# currentplank.net
KiCad netlist of a schematic drawn in EAGLE
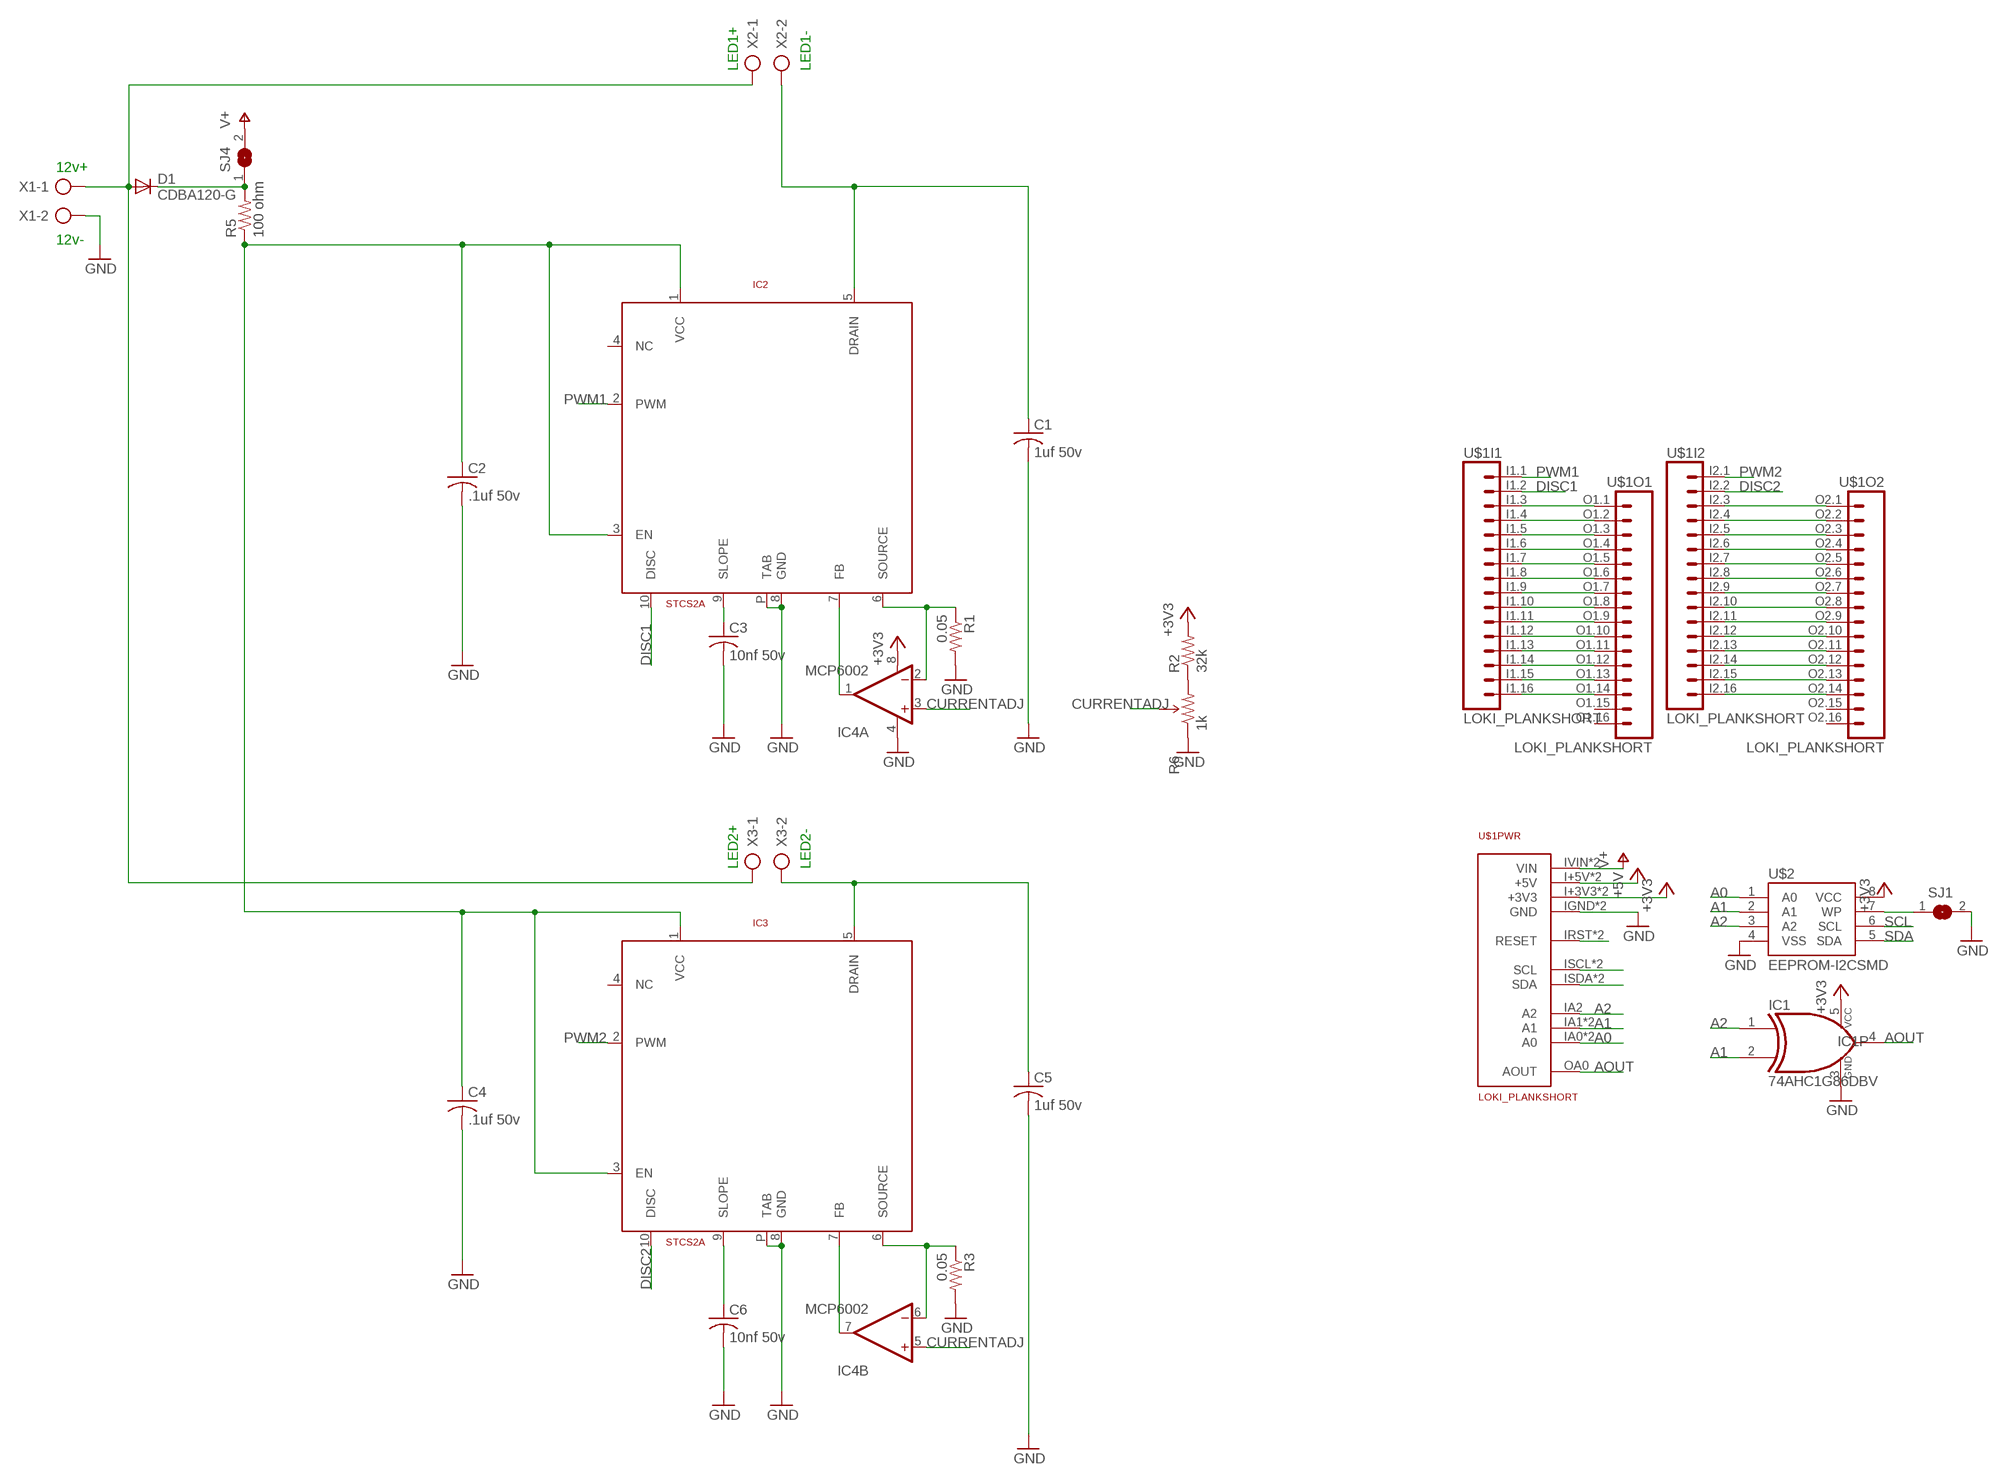
[diagram p0: schematic, sheet 1]

(export (version "E")
  (design (tool "Eeschema 10.0.6"))
  (components
    (comp (ref "C1")
      (value "1uf 50v")
      (footprint "eagle-import:C0805")
      (libsource (lib "eagle-import") (part "C-USC0805"))
    )
    (comp (ref "C2")
      (value ".1uf 50v")
      (footprint "eagle-import:C0805")
      (libsource (lib "eagle-import") (part "C-USC0805"))
    )
    (comp (ref "C3")
      (value "10nf 50v")
      (footprint "eagle-import:C0805")
      (libsource (lib "eagle-import") (part "C-USC0805"))
    )
    (comp (ref "C4")
      (value ".1uf 50v")
      (footprint "eagle-import:C0805")
      (libsource (lib "eagle-import") (part "C-USC0805"))
    )
    (comp (ref "C5")
      (value "1uf 50v")
      (footprint "eagle-import:C0805")
      (libsource (lib "eagle-import") (part "C-USC0805"))
    )
    (comp (ref "C6")
      (value "10nf 50v")
      (footprint "eagle-import:C0805")
      (libsource (lib "eagle-import") (part "C-USC0805"))
    )
    (comp (ref "D1")
      (value "CDBA120-G")
      (footprint "eagle-import:SMA-DIODE")
      (libsource (lib "eagle-import") (part "DIODESMA"))
    )
    (comp (ref "IC1")
      (value "74AHC1G86DBV")
      (footprint "eagle-import:SOT23-5")
      (libsource (lib "eagle-import") (part "741G86DBVAHC"))
    )
    (comp (ref "IC2")
      (value "STCS2A")
      (footprint "eagle-import:STCS2A_POWER-SO10")
      (libsource (lib "eagle-import") (part "STCS2A_STCS2A"))
    )
    (comp (ref "IC3")
      (value "STCS2A")
      (footprint "eagle-import:STCS2A_POWER-SO10")
      (libsource (lib "eagle-import") (part "STCS2A_STCS2A"))
    )
    (comp (ref "IC4")
      (value "MCP6002")
      (footprint "eagle-import:SO08")
      (libsource (lib "eagle-import") (part "OPAMP-DUALU"))
    )
    (comp (ref "R1")
      (value "0.05")
      (footprint "eagle-import:1206")
      (libsource (lib "eagle-import") (part "RESISTOR1206"))
    )
    (comp (ref "R2")
      (value "32k")
      (footprint "eagle-import:0805")
      (libsource (lib "eagle-import") (part "RESISTOR0805-RES"))
    )
    (comp (ref "R3")
      (value "0.05")
      (footprint "eagle-import:1206")
      (libsource (lib "eagle-import") (part "RESISTOR1206"))
    )
    (comp (ref "R5")
      (value "100 ohm")
      (footprint "eagle-import:0805")
      (libsource (lib "eagle-import") (part "RESISTOR0805-RES"))
    )
    (comp (ref "R6")
      (value "1k")
      (footprint "eagle-import:TRIMPOT-3MM-2")
      (libsource (lib "eagle-import") (part "TRIMPOT3MM-2"))
    )
    (comp (ref "SJ1") (value "SJ") (footprint "eagle-import:SJ") (libsource (lib "eagle-import") (part "SJ")))
    (comp (ref "SJ4") (value "SJ") (footprint "eagle-import:SJ") (libsource (lib "eagle-import") (part "SJ")))
    (comp (ref "U$1")
      (value "LOKI_PLANKSHORT")
      (footprint "eagle-import:PLANK_SHORT")
      (libsource (lib "eagle-import") (part "LOKI_PLANKSHORT"))
    )
    (comp (ref "U$2")
      (value "EEPROM-I2CSMD")
      (footprint "eagle-import:SO08")
      (libsource (lib "eagle-import") (part "EEPROM-I2CSMD"))
    )
    (comp (ref "X1")
      (value "AK500/2-H")
      (footprint "eagle-import:AK500_2-H")
      (libsource (lib "eagle-import") (part "AK500/2-H"))
    )
    (comp (ref "X2")
      (value "AK500/2-H")
      (footprint "eagle-import:AK500_2-H")
      (libsource (lib "eagle-import") (part "AK500/2-H"))
    )
    (comp (ref "X3")
      (value "AK500/2-H")
      (footprint "eagle-import:AK500_2-H")
      (libsource (lib "eagle-import") (part "AK500/2-H"))
    )
  )
  (nets
    (net (code "1") (name "+3V3") (class "Default")
      (node (ref "IC1") (pin "5") (pinfunction "VCC_5") (pintype "power_in"))
      (node (ref "IC4") (pin "8") (pinfunction "V+_8") (pintype "power_in"))
      (node (ref "R2") (pin "2") (pinfunction "2_2") (pintype "passive"))
      (node (ref "U$1") (pin "I+3V3") (pinfunction "+3V3_I+3V3") (pintype "power_in"))
      (node (ref "U$1") (pin "O+3V3") (pinfunction "+3V3_O+3V3") (pintype "power_in"))
      (node (ref "U$2") (pin "8") (pinfunction "VCC_8") (pintype "power_in"))
    )
    (net (code "2") (name "+5V") (class "Default")
      (node (ref "U$1") (pin "I+5V") (pinfunction "+5V_I+5V") (pintype "power_in"))
      (node (ref "U$1") (pin "O+5V") (pinfunction "+5V_O+5V") (pintype "power_in"))
    )
    (net (code "3") (name "/A0") (class "Default")
      (node (ref "U$1") (pin "IA0") (pinfunction "A0_IA0") (pintype "output"))
      (node (ref "U$1") (pin "OA1") (pinfunction "A0_OA1") (pintype "output"))
      (node (ref "U$2") (pin "1") (pinfunction "A0_1") (pintype "bidirectional"))
    )
    (net (code "4") (name "/A1") (class "Default")
      (node (ref "IC1") (pin "2") (pinfunction "I1_2") (pintype "input"))
      (node (ref "U$1") (pin "IA1") (pinfunction "A1_IA1") (pintype "output"))
      (node (ref "U$1") (pin "OA2") (pinfunction "A1_OA2") (pintype "output"))
      (node (ref "U$2") (pin "2") (pinfunction "A1_2") (pintype "bidirectional"))
    )
    (net (code "5") (name "/A2") (class "Default")
      (node (ref "IC1") (pin "1") (pinfunction "I0_1") (pintype "input"))
      (node (ref "U$1") (pin "IA2") (pinfunction "A2_IA2") (pintype "output"))
      (node (ref "U$2") (pin "3") (pinfunction "A2_3") (pintype "bidirectional"))
    )
    (net (code "6") (name "/AOUT") (class "Default")
      (node (ref "IC1") (pin "4") (pinfunction "O_4") (pintype "output"))
      (node (ref "U$1") (pin "OA0") (pinfunction "AOUT_OA0") (pintype "input"))
    )
    (net (code "7") (name "/CURRENTADJ") (class "Default")
      (node (ref "IC4") (pin "3") (pinfunction "+IN_3") (pintype "input"))
      (node (ref "IC4") (pin "5") (pinfunction "+IN_5") (pintype "input"))
      (node (ref "R6") (pin "2") (pinfunction "WIPER_2") (pintype "passive"))
    )
    (net (code "8") (name "/DISC1") (class "Default")
      (node (ref "IC2") (pin "10") (pinfunction "DISC_10") (pintype "output"))
      (node (ref "U$1") (pin "I1.2") (pinfunction "2_I1.2") (pintype "passive"))
    )
    (net (code "9") (name "/DISC2") (class "Default")
      (node (ref "IC3") (pin "10") (pinfunction "DISC_10") (pintype "output"))
      (node (ref "U$1") (pin "I2.2") (pinfunction "2_I2.2") (pintype "passive"))
    )
    (net (code "10") (name "/PWM1") (class "Default")
      (node (ref "IC2") (pin "2") (pinfunction "PWM_2") (pintype "input"))
      (node (ref "U$1") (pin "I1.1") (pinfunction "1_I1.1") (pintype "passive"))
    )
    (net (code "11") (name "/PWM2") (class "Default")
      (node (ref "IC3") (pin "2") (pinfunction "PWM_2") (pintype "input"))
      (node (ref "U$1") (pin "I2.1") (pinfunction "1_I2.1") (pintype "passive"))
    )
    (net (code "12") (name "/SCL") (class "Default")
      (node (ref "U$1") (pin "ISCL") (pinfunction "SCL_ISCL") (pintype "bidirectional"))
      (node (ref "U$1") (pin "OSCL") (pinfunction "SCL_OSCL") (pintype "bidirectional"))
      (node (ref "U$2") (pin "6") (pinfunction "SCL_6") (pintype "bidirectional"))
    )
    (net (code "13") (name "/SDA") (class "Default")
      (node (ref "U$1") (pin "ISDA") (pinfunction "SDA_ISDA") (pintype "bidirectional"))
      (node (ref "U$1") (pin "OSDA") (pinfunction "SDA_OSDA") (pintype "bidirectional"))
      (node (ref "U$2") (pin "5") (pinfunction "SDA_5") (pintype "bidirectional"))
    )
    (net (code "14") (name "GND") (class "Default")
      (node (ref "C1") (pin "2") (pinfunction "2_2") (pintype "passive"))
      (node (ref "C2") (pin "2") (pinfunction "2_2") (pintype "passive"))
      (node (ref "C3") (pin "2") (pinfunction "2_2") (pintype "passive"))
      (node (ref "C4") (pin "2") (pinfunction "2_2") (pintype "passive"))
      (node (ref "C5") (pin "2") (pinfunction "2_2") (pintype "passive"))
      (node (ref "C6") (pin "2") (pinfunction "2_2") (pintype "passive"))
      (node (ref "IC1") (pin "3") (pinfunction "GND_3") (pintype "power_in"))
      (node (ref "IC2") (pin "8") (pinfunction "GND_8") (pintype "power_in"))
      (node (ref "IC2") (pin "P") (pinfunction "TAB_P") (pintype "power_in"))
      (node (ref "IC3") (pin "8") (pinfunction "GND_8") (pintype "power_in"))
      (node (ref "IC3") (pin "P") (pinfunction "TAB_P") (pintype "power_in"))
      (node (ref "IC4") (pin "4") (pinfunction "V-_4") (pintype "power_in"))
      (node (ref "R1") (pin "2") (pinfunction "2_2") (pintype "passive"))
      (node (ref "R3") (pin "2") (pinfunction "2_2") (pintype "passive"))
      (node (ref "R6") (pin "1") (pinfunction "CCW_1") (pintype "passive"))
      (node (ref "SJ1") (pin "2") (pinfunction "2_2") (pintype "passive"))
      (node (ref "U$1") (pin "IGND") (pinfunction "GND_IGND") (pintype "power_in"))
      (node (ref "U$1") (pin "OGND") (pinfunction "GND_OGND") (pintype "power_in"))
      (node (ref "U$2") (pin "4") (pinfunction "VSS_4") (pintype "power_in"))
      (node (ref "X1") (pin "2") (pinfunction "KL_2") (pintype "passive"))
    )
    (net (code "15") (name "Net-(D1-PadC)") (class "Default")
      (node (ref "D1") (pin "C") (pinfunction "C_C") (pintype "passive"))
      (node (ref "R5") (pin "2") (pinfunction "2_2") (pintype "passive"))
      (node (ref "SJ4") (pin "1") (pinfunction "1_1") (pintype "passive"))
    )
    (net (code "16") (name "Net-(IC2-DRAIN)") (class "Default")
      (node (ref "C1") (pin "1") (pinfunction "1_1") (pintype "passive"))
      (node (ref "IC2") (pin "5") (pinfunction "DRAIN_5") (pintype "input"))
      (node (ref "X2") (pin "2") (pinfunction "KL_2") (pintype "passive"))
    )
    (net (code "17") (name "Net-(IC2-EN)") (class "Default")
      (node (ref "C2") (pin "1") (pinfunction "1_1") (pintype "passive"))
      (node (ref "C4") (pin "1") (pinfunction "1_1") (pintype "passive"))
      (node (ref "IC2") (pin "1") (pinfunction "VCC_1") (pintype "power_in"))
      (node (ref "IC2") (pin "3") (pinfunction "EN_3") (pintype "input"))
      (node (ref "IC3") (pin "1") (pinfunction "VCC_1") (pintype "power_in"))
      (node (ref "IC3") (pin "3") (pinfunction "EN_3") (pintype "input"))
      (node (ref "R5") (pin "1") (pinfunction "1_1") (pintype "passive"))
    )
    (net (code "18") (name "Net-(IC2-FB)") (class "Default")
      (node (ref "IC2") (pin "7") (pinfunction "FB_7") (pintype "input"))
      (node (ref "IC4") (pin "1") (pinfunction "OUT_1") (pintype "output"))
    )
    (net (code "19") (name "Net-(IC2-SLOPE)") (class "Default")
      (node (ref "C3") (pin "1") (pinfunction "1_1") (pintype "passive"))
      (node (ref "IC2") (pin "9") (pinfunction "SLOPE_9") (pintype "passive"))
    )
    (net (code "20") (name "Net-(IC2-SOURCE)") (class "Default")
      (node (ref "IC2") (pin "6") (pinfunction "SOURCE_6") (pintype "output"))
      (node (ref "IC4") (pin "2") (pinfunction "-IN_2") (pintype "input"))
      (node (ref "R1") (pin "1") (pinfunction "1_1") (pintype "passive"))
    )
    (net (code "21") (name "Net-(IC3-DRAIN)") (class "Default")
      (node (ref "C5") (pin "1") (pinfunction "1_1") (pintype "passive"))
      (node (ref "IC3") (pin "5") (pinfunction "DRAIN_5") (pintype "input"))
      (node (ref "X3") (pin "2") (pinfunction "KL_2") (pintype "passive"))
    )
    (net (code "22") (name "Net-(IC3-FB)") (class "Default")
      (node (ref "IC3") (pin "7") (pinfunction "FB_7") (pintype "input"))
      (node (ref "IC4") (pin "7") (pinfunction "OUT_7") (pintype "output"))
    )
    (net (code "23") (name "Net-(IC3-SLOPE)") (class "Default")
      (node (ref "C6") (pin "1") (pinfunction "1_1") (pintype "passive"))
      (node (ref "IC3") (pin "9") (pinfunction "SLOPE_9") (pintype "passive"))
    )
    (net (code "24") (name "Net-(IC3-SOURCE)") (class "Default")
      (node (ref "IC3") (pin "6") (pinfunction "SOURCE_6") (pintype "output"))
      (node (ref "IC4") (pin "6") (pinfunction "-IN_6") (pintype "input"))
      (node (ref "R3") (pin "1") (pinfunction "1_1") (pintype "passive"))
    )
    (net (code "25") (name "Net-(R6-CW)") (class "Default")
      (node (ref "R2") (pin "1") (pinfunction "1_1") (pintype "passive"))
      (node (ref "R6") (pin "3") (pinfunction "CW_3") (pintype "passive"))
    )
    (net (code "26") (name "Net-(U$1A-3)") (class "Default")
      (node (ref "U$1") (pin "I1.3") (pinfunction "3_I1.3") (pintype "passive"))
      (node (ref "U$1") (pin "O1.1") (pinfunction "1_O1.1") (pintype "passive"))
    )
    (net (code "27") (name "Net-(U$1A-4)") (class "Default")
      (node (ref "U$1") (pin "I1.4") (pinfunction "4_I1.4") (pintype "passive"))
      (node (ref "U$1") (pin "O1.2") (pinfunction "2_O1.2") (pintype "passive"))
    )
    (net (code "28") (name "Net-(U$1A-5)") (class "Default")
      (node (ref "U$1") (pin "I1.5") (pinfunction "5_I1.5") (pintype "passive"))
      (node (ref "U$1") (pin "O1.3") (pinfunction "3_O1.3") (pintype "passive"))
    )
    (net (code "29") (name "Net-(U$1A-6)") (class "Default")
      (node (ref "U$1") (pin "I1.6") (pinfunction "6_I1.6") (pintype "passive"))
      (node (ref "U$1") (pin "O1.4") (pinfunction "4_O1.4") (pintype "passive"))
    )
    (net (code "30") (name "Net-(U$1A-7)") (class "Default")
      (node (ref "U$1") (pin "I1.7") (pinfunction "7_I1.7") (pintype "passive"))
      (node (ref "U$1") (pin "O1.5") (pinfunction "5_O1.5") (pintype "passive"))
    )
    (net (code "31") (name "Net-(U$1A-8)") (class "Default")
      (node (ref "U$1") (pin "I1.8") (pinfunction "8_I1.8") (pintype "passive"))
      (node (ref "U$1") (pin "O1.6") (pinfunction "6_O1.6") (pintype "passive"))
    )
    (net (code "32") (name "Net-(U$1A-9)") (class "Default")
      (node (ref "U$1") (pin "I1.9") (pinfunction "9_I1.9") (pintype "passive"))
      (node (ref "U$1") (pin "O1.7") (pinfunction "7_O1.7") (pintype "passive"))
    )
    (net (code "33") (name "Net-(U$1A-10)") (class "Default")
      (node (ref "U$1") (pin "I1.10") (pinfunction "10_I1.10") (pintype "passive"))
      (node (ref "U$1") (pin "O1.8") (pinfunction "8_O1.8") (pintype "passive"))
    )
    (net (code "34") (name "Net-(U$1A-11)") (class "Default")
      (node (ref "U$1") (pin "I1.11") (pinfunction "11_I1.11") (pintype "passive"))
      (node (ref "U$1") (pin "O1.9") (pinfunction "9_O1.9") (pintype "passive"))
    )
    (net (code "35") (name "Net-(U$1A-12)") (class "Default")
      (node (ref "U$1") (pin "I1.12") (pinfunction "12_I1.12") (pintype "passive"))
      (node (ref "U$1") (pin "O1.10") (pinfunction "10_O1.10") (pintype "passive"))
    )
    (net (code "36") (name "Net-(U$1A-13)") (class "Default")
      (node (ref "U$1") (pin "I1.13") (pinfunction "13_I1.13") (pintype "passive"))
      (node (ref "U$1") (pin "O1.11") (pinfunction "11_O1.11") (pintype "passive"))
    )
    (net (code "37") (name "Net-(U$1A-14)") (class "Default")
      (node (ref "U$1") (pin "I1.14") (pinfunction "14_I1.14") (pintype "passive"))
      (node (ref "U$1") (pin "O1.12") (pinfunction "12_O1.12") (pintype "passive"))
    )
    (net (code "38") (name "Net-(U$1A-15)") (class "Default")
      (node (ref "U$1") (pin "I1.15") (pinfunction "15_I1.15") (pintype "passive"))
      (node (ref "U$1") (pin "O1.13") (pinfunction "13_O1.13") (pintype "passive"))
    )
    (net (code "39") (name "Net-(U$1A-16)") (class "Default")
      (node (ref "U$1") (pin "I1.16") (pinfunction "16_I1.16") (pintype "passive"))
      (node (ref "U$1") (pin "O1.14") (pinfunction "14_O1.14") (pintype "passive"))
    )
    (net (code "40") (name "Net-(U$1B-3)") (class "Default")
      (node (ref "U$1") (pin "I2.3") (pinfunction "3_I2.3") (pintype "passive"))
      (node (ref "U$1") (pin "O2.1") (pinfunction "1_O2.1") (pintype "passive"))
    )
    (net (code "41") (name "Net-(U$1B-4)") (class "Default")
      (node (ref "U$1") (pin "I2.4") (pinfunction "4_I2.4") (pintype "passive"))
      (node (ref "U$1") (pin "O2.2") (pinfunction "2_O2.2") (pintype "passive"))
    )
    (net (code "42") (name "Net-(U$1B-5)") (class "Default")
      (node (ref "U$1") (pin "I2.5") (pinfunction "5_I2.5") (pintype "passive"))
      (node (ref "U$1") (pin "O2.3") (pinfunction "3_O2.3") (pintype "passive"))
    )
    (net (code "43") (name "Net-(U$1B-6)") (class "Default")
      (node (ref "U$1") (pin "I2.6") (pinfunction "6_I2.6") (pintype "passive"))
      (node (ref "U$1") (pin "O2.4") (pinfunction "4_O2.4") (pintype "passive"))
    )
    (net (code "44") (name "Net-(U$1B-7)") (class "Default")
      (node (ref "U$1") (pin "I2.7") (pinfunction "7_I2.7") (pintype "passive"))
      (node (ref "U$1") (pin "O2.5") (pinfunction "5_O2.5") (pintype "passive"))
    )
    (net (code "45") (name "Net-(U$1B-8)") (class "Default")
      (node (ref "U$1") (pin "I2.8") (pinfunction "8_I2.8") (pintype "passive"))
      (node (ref "U$1") (pin "O2.6") (pinfunction "6_O2.6") (pintype "passive"))
    )
    (net (code "46") (name "Net-(U$1B-9)") (class "Default")
      (node (ref "U$1") (pin "I2.9") (pinfunction "9_I2.9") (pintype "passive"))
      (node (ref "U$1") (pin "O2.7") (pinfunction "7_O2.7") (pintype "passive"))
    )
    (net (code "47") (name "Net-(U$1B-10)") (class "Default")
      (node (ref "U$1") (pin "I2.10") (pinfunction "10_I2.10") (pintype "passive"))
      (node (ref "U$1") (pin "O2.8") (pinfunction "8_O2.8") (pintype "passive"))
    )
    (net (code "48") (name "Net-(U$1B-11)") (class "Default")
      (node (ref "U$1") (pin "I2.11") (pinfunction "11_I2.11") (pintype "passive"))
      (node (ref "U$1") (pin "O2.9") (pinfunction "9_O2.9") (pintype "passive"))
    )
    (net (code "49") (name "Net-(U$1B-12)") (class "Default")
      (node (ref "U$1") (pin "I2.12") (pinfunction "12_I2.12") (pintype "passive"))
      (node (ref "U$1") (pin "O2.10") (pinfunction "10_O2.10") (pintype "passive"))
    )
    (net (code "50") (name "Net-(U$1B-13)") (class "Default")
      (node (ref "U$1") (pin "I2.13") (pinfunction "13_I2.13") (pintype "passive"))
      (node (ref "U$1") (pin "O2.11") (pinfunction "11_O2.11") (pintype "passive"))
    )
    (net (code "51") (name "Net-(U$1B-14)") (class "Default")
      (node (ref "U$1") (pin "I2.14") (pinfunction "14_I2.14") (pintype "passive"))
      (node (ref "U$1") (pin "O2.12") (pinfunction "12_O2.12") (pintype "passive"))
    )
    (net (code "52") (name "Net-(U$1B-15)") (class "Default")
      (node (ref "U$1") (pin "I2.15") (pinfunction "15_I2.15") (pintype "passive"))
      (node (ref "U$1") (pin "O2.13") (pinfunction "13_O2.13") (pintype "passive"))
    )
    (net (code "53") (name "Net-(U$1B-16)") (class "Default")
      (node (ref "U$1") (pin "I2.16") (pinfunction "16_I2.16") (pintype "passive"))
      (node (ref "U$1") (pin "O2.14") (pinfunction "14_O2.14") (pintype "passive"))
    )
    (net (code "54") (name "Net-(U$1E-RESET-PadIRST)") (class "Default")
      (node (ref "U$1") (pin "IRST") (pinfunction "RESET_IRST") (pintype "input"))
      (node (ref "U$1") (pin "ORST") (pinfunction "RESET_ORST") (pintype "input"))
    )
    (net (code "55") (name "Net-(U$2-WP)") (class "Default")
      (node (ref "SJ1") (pin "1") (pinfunction "1_1") (pintype "passive"))
      (node (ref "U$2") (pin "7") (pinfunction "WP_7") (pintype "bidirectional"))
    )
    (net (code "56") (name "Net-(X1A-KL)") (class "Default")
      (node (ref "D1") (pin "A") (pinfunction "A_A") (pintype "passive"))
      (node (ref "X1") (pin "1") (pinfunction "KL_1") (pintype "passive"))
      (node (ref "X2") (pin "1") (pinfunction "KL_1") (pintype "passive"))
      (node (ref "X3") (pin "1") (pinfunction "KL_1") (pintype "passive"))
    )
    (net (code "57") (name "V+") (class "Default")
      (node (ref "SJ4") (pin "2") (pinfunction "2_2") (pintype "passive"))
      (node (ref "U$1") (pin "IVIN") (pinfunction "VIN_IVIN") (pintype "power_in"))
      (node (ref "U$1") (pin "OVIN") (pinfunction "VIN_OVIN") (pintype "power_in"))
    )
    (net (code "58") (name "unconnected-(IC2-NC-Pad4)") (class "Default")
      (node (ref "IC2") (pin "4") (pinfunction "NC_4") (pintype "no_connect"))
    )
    (net (code "59") (name "unconnected-(IC3-NC-Pad4)") (class "Default")
      (node (ref "IC3") (pin "4") (pinfunction "NC_4") (pintype "no_connect"))
    )
    (net (code "60") (name "unconnected-(U$1C-15-PadO1.15)") (class "Default")
      (node (ref "U$1") (pin "O1.15") (pinfunction "15_O1.15") (pintype "passive"))
    )
    (net (code "61") (name "unconnected-(U$1C-16-PadO1.16)") (class "Default")
      (node (ref "U$1") (pin "O1.16") (pinfunction "16_O1.16") (pintype "passive"))
    )
    (net (code "62") (name "unconnected-(U$1D-15-PadO2.15)") (class "Default")
      (node (ref "U$1") (pin "O2.15") (pinfunction "15_O2.15") (pintype "passive"))
    )
    (net (code "63") (name "unconnected-(U$1D-16-PadO2.16)") (class "Default")
      (node (ref "U$1") (pin "O2.16") (pinfunction "16_O2.16") (pintype "passive"))
    )
  )
)
